# SensorPCBA_v0_1.net
KiCad netlist of a schematic drawn in Altium Designer
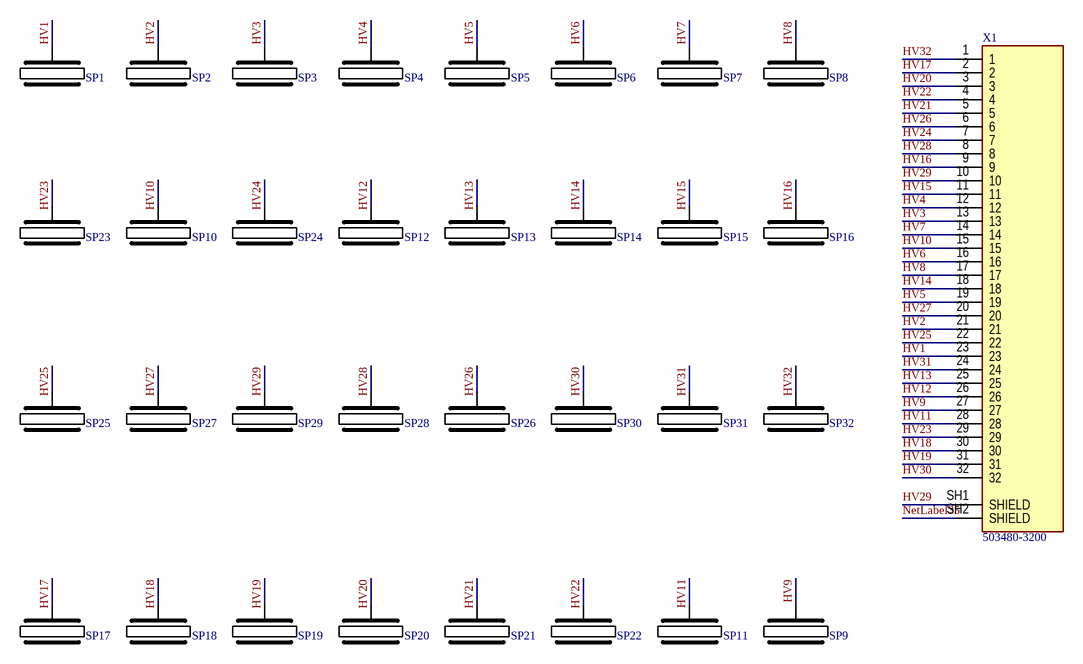
[diagram p0: SensorPCBA_v0.1.SchDoc]

(export (version "E")
  (design (tool "Eeschema 10.0.6"))
  (components
    (comp (ref "SP1")
      (value "SensorPAD")
      (footprint "Pump_via")
      (libsource (lib "SensorPCBA") (part "SensorPAD"))
    )
    (comp (ref "SP2")
      (value "SensorPAD")
      (footprint "Pump_via")
      (libsource (lib "SensorPCBA") (part "SensorPAD"))
    )
    (comp (ref "SP3")
      (value "SensorPAD")
      (footprint "Pump_via")
      (libsource (lib "SensorPCBA") (part "SensorPAD"))
    )
    (comp (ref "SP4")
      (value "SensorPAD")
      (footprint "Pump_via")
      (libsource (lib "SensorPCBA") (part "SensorPAD"))
    )
    (comp (ref "SP5")
      (value "SensorPAD")
      (footprint "Pump_via")
      (libsource (lib "SensorPCBA") (part "SensorPAD"))
    )
    (comp (ref "SP6")
      (value "SensorPAD")
      (footprint "Pump_via")
      (libsource (lib "SensorPCBA") (part "SensorPAD"))
    )
    (comp (ref "SP7")
      (value "SensorPAD")
      (footprint "Pump_via")
      (libsource (lib "SensorPCBA") (part "SensorPAD"))
    )
    (comp (ref "SP8")
      (value "SensorPAD")
      (footprint "Pump_via")
      (libsource (lib "SensorPCBA") (part "SensorPAD"))
    )
    (comp (ref "SP9")
      (value "SensorPAD")
      (footprint "Pump_via")
      (libsource (lib "SensorPCBA") (part "SensorPAD"))
    )
    (comp (ref "SP10")
      (value "SensorPAD")
      (footprint "Pump_via")
      (libsource (lib "SensorPCBA") (part "SensorPAD"))
    )
    (comp (ref "SP11")
      (value "SensorPAD")
      (footprint "Pump_via")
      (libsource (lib "SensorPCBA") (part "SensorPAD"))
    )
    (comp (ref "SP12")
      (value "SensorPAD")
      (footprint "Pump_via")
      (libsource (lib "SensorPCBA") (part "SensorPAD"))
    )
    (comp (ref "SP13")
      (value "SensorPAD")
      (footprint "Pump_via")
      (libsource (lib "SensorPCBA") (part "SensorPAD"))
    )
    (comp (ref "SP14")
      (value "SensorPAD")
      (footprint "Pump_via")
      (libsource (lib "SensorPCBA") (part "SensorPAD"))
    )
    (comp (ref "SP15")
      (value "SensorPAD")
      (footprint "Pump_via")
      (libsource (lib "SensorPCBA") (part "SensorPAD"))
    )
    (comp (ref "SP16")
      (value "SensorPAD")
      (footprint "Pump_via")
      (libsource (lib "SensorPCBA") (part "SensorPAD"))
    )
    (comp (ref "SP17")
      (value "SensorPAD")
      (footprint "Pump_via")
      (libsource (lib "SensorPCBA") (part "SensorPAD"))
    )
    (comp (ref "SP18")
      (value "SensorPAD")
      (footprint "Pump_via")
      (libsource (lib "SensorPCBA") (part "SensorPAD"))
    )
    (comp (ref "SP19")
      (value "SensorPAD")
      (footprint "Pump_via")
      (libsource (lib "SensorPCBA") (part "SensorPAD"))
    )
    (comp (ref "SP20")
      (value "SensorPAD")
      (footprint "Pump_via")
      (libsource (lib "SensorPCBA") (part "SensorPAD"))
    )
    (comp (ref "SP21")
      (value "SensorPAD")
      (footprint "Pump_via")
      (libsource (lib "SensorPCBA") (part "SensorPAD"))
    )
    (comp (ref "SP22")
      (value "SensorPAD")
      (footprint "Pump_via")
      (libsource (lib "SensorPCBA") (part "SensorPAD"))
    )
    (comp (ref "SP23")
      (value "SensorPAD")
      (footprint "Pump_via")
      (libsource (lib "SensorPCBA") (part "SensorPAD"))
    )
    (comp (ref "SP24")
      (value "SensorPAD")
      (footprint "Pump_via")
      (libsource (lib "SensorPCBA") (part "SensorPAD"))
    )
    (comp (ref "SP25")
      (value "SensorPAD")
      (footprint "Pump_via")
      (libsource (lib "SensorPCBA") (part "SensorPAD"))
    )
    (comp (ref "SP26")
      (value "SensorPAD")
      (footprint "Pump_via")
      (libsource (lib "SensorPCBA") (part "SensorPAD"))
    )
    (comp (ref "SP27")
      (value "SensorPAD")
      (footprint "Pump_via")
      (libsource (lib "SensorPCBA") (part "SensorPAD"))
    )
    (comp (ref "SP28")
      (value "SensorPAD")
      (footprint "Pump_via")
      (libsource (lib "SensorPCBA") (part "SensorPAD"))
    )
    (comp (ref "SP29")
      (value "SensorPAD")
      (footprint "Pump_via")
      (libsource (lib "SensorPCBA") (part "SensorPAD"))
    )
    (comp (ref "SP30")
      (value "SensorPAD")
      (footprint "Pump_via")
      (libsource (lib "SensorPCBA") (part "SensorPAD"))
    )
    (comp (ref "SP31")
      (value "SensorPAD")
      (footprint "Pump_via")
      (libsource (lib "SensorPCBA") (part "SensorPAD"))
    )
    (comp (ref "SP32")
      (value "SensorPAD")
      (footprint "Pump_via")
      (libsource (lib "SensorPCBA") (part "SensorPAD"))
    )
    (comp (ref "X1")
      (value "503480-3200")
      (footprint "MOLEX_503480-3200")
      (description "32 Position FFC, FPC Connector Contacts, Top and Bottom 0.020 (0.50mm) Surface Mount, Right Angle")
      (fields (field (name "MF") "Molex") (field (name "MP") "5034803200"))
      (libsource (lib "SensorPCBA") (part "503480-3200"))
    )
  )
  (nets
    (net (code "1") (name "/HV1") (class "Default")
      (node (ref "SP1") (pin "1") (pinfunction "Atop_1") (pintype "passive"))
      (node (ref "X1") (pin "23") (pinfunction "23_23") (pintype "passive"))
    )
    (net (code "2") (name "/HV2") (class "Default")
      (node (ref "SP2") (pin "1") (pinfunction "Atop_1") (pintype "passive"))
      (node (ref "X1") (pin "21") (pinfunction "21_21") (pintype "passive"))
    )
    (net (code "3") (name "/HV3") (class "Default")
      (node (ref "SP3") (pin "1") (pinfunction "Atop_1") (pintype "passive"))
      (node (ref "X1") (pin "13") (pinfunction "13_13") (pintype "passive"))
    )
    (net (code "4") (name "/HV4") (class "Default")
      (node (ref "SP4") (pin "1") (pinfunction "Atop_1") (pintype "passive"))
      (node (ref "X1") (pin "12") (pinfunction "12_12") (pintype "passive"))
    )
    (net (code "5") (name "/HV5") (class "Default")
      (node (ref "SP5") (pin "1") (pinfunction "Atop_1") (pintype "passive"))
      (node (ref "X1") (pin "19") (pinfunction "19_19") (pintype "passive"))
    )
    (net (code "6") (name "/HV6") (class "Default")
      (node (ref "SP6") (pin "1") (pinfunction "Atop_1") (pintype "passive"))
      (node (ref "X1") (pin "16") (pinfunction "16_16") (pintype "passive"))
    )
    (net (code "7") (name "/HV7") (class "Default")
      (node (ref "SP7") (pin "1") (pinfunction "Atop_1") (pintype "passive"))
      (node (ref "X1") (pin "14") (pinfunction "14_14") (pintype "passive"))
    )
    (net (code "8") (name "/HV8") (class "Default")
      (node (ref "SP8") (pin "1") (pinfunction "Atop_1") (pintype "passive"))
      (node (ref "X1") (pin "17") (pinfunction "17_17") (pintype "passive"))
    )
    (net (code "9") (name "/HV9") (class "Default")
      (node (ref "SP9") (pin "1") (pinfunction "Atop_1") (pintype "passive"))
      (node (ref "X1") (pin "27") (pinfunction "27_27") (pintype "passive"))
    )
    (net (code "10") (name "/HV10") (class "Default")
      (node (ref "SP10") (pin "1") (pinfunction "Atop_1") (pintype "passive"))
      (node (ref "X1") (pin "15") (pinfunction "15_15") (pintype "passive"))
    )
    (net (code "11") (name "/HV11") (class "Default")
      (node (ref "SP11") (pin "1") (pinfunction "Atop_1") (pintype "passive"))
      (node (ref "X1") (pin "28") (pinfunction "28_28") (pintype "passive"))
    )
    (net (code "12") (name "/HV12") (class "Default")
      (node (ref "SP12") (pin "1") (pinfunction "Atop_1") (pintype "passive"))
      (node (ref "X1") (pin "26") (pinfunction "26_26") (pintype "passive"))
    )
    (net (code "13") (name "/HV13") (class "Default")
      (node (ref "SP13") (pin "1") (pinfunction "Atop_1") (pintype "passive"))
      (node (ref "X1") (pin "25") (pinfunction "25_25") (pintype "passive"))
    )
    (net (code "14") (name "/HV14") (class "Default")
      (node (ref "SP14") (pin "1") (pinfunction "Atop_1") (pintype "passive"))
      (node (ref "X1") (pin "18") (pinfunction "18_18") (pintype "passive"))
    )
    (net (code "15") (name "/HV15") (class "Default")
      (node (ref "SP15") (pin "1") (pinfunction "Atop_1") (pintype "passive"))
      (node (ref "X1") (pin "11") (pinfunction "11_11") (pintype "passive"))
    )
    (net (code "16") (name "/HV16") (class "Default")
      (node (ref "SP16") (pin "1") (pinfunction "Atop_1") (pintype "passive"))
      (node (ref "X1") (pin "9") (pinfunction "9_9") (pintype "passive"))
    )
    (net (code "17") (name "/HV17") (class "Default")
      (node (ref "SP17") (pin "1") (pinfunction "Atop_1") (pintype "passive"))
      (node (ref "X1") (pin "2") (pinfunction "2_2") (pintype "passive"))
    )
    (net (code "18") (name "/HV18") (class "Default")
      (node (ref "SP18") (pin "1") (pinfunction "Atop_1") (pintype "passive"))
      (node (ref "X1") (pin "30") (pinfunction "30_30") (pintype "passive"))
    )
    (net (code "19") (name "/HV19") (class "Default")
      (node (ref "SP19") (pin "1") (pinfunction "Atop_1") (pintype "passive"))
      (node (ref "X1") (pin "31") (pinfunction "31_31") (pintype "passive"))
    )
    (net (code "20") (name "/HV20") (class "Default")
      (node (ref "SP20") (pin "1") (pinfunction "Atop_1") (pintype "passive"))
      (node (ref "X1") (pin "3") (pinfunction "3_3") (pintype "passive"))
    )
    (net (code "21") (name "/HV21") (class "Default")
      (node (ref "SP21") (pin "1") (pinfunction "Atop_1") (pintype "passive"))
      (node (ref "X1") (pin "5") (pinfunction "5_5") (pintype "passive"))
    )
    (net (code "22") (name "/HV22") (class "Default")
      (node (ref "SP22") (pin "1") (pinfunction "Atop_1") (pintype "passive"))
      (node (ref "X1") (pin "4") (pinfunction "4_4") (pintype "passive"))
    )
    (net (code "23") (name "/HV23") (class "Default")
      (node (ref "SP23") (pin "1") (pinfunction "Atop_1") (pintype "passive"))
      (node (ref "X1") (pin "29") (pinfunction "29_29") (pintype "passive"))
    )
    (net (code "24") (name "/HV24") (class "Default")
      (node (ref "SP24") (pin "1") (pinfunction "Atop_1") (pintype "passive"))
      (node (ref "X1") (pin "7") (pinfunction "7_7") (pintype "passive"))
    )
    (net (code "25") (name "/HV25") (class "Default")
      (node (ref "SP25") (pin "1") (pinfunction "Atop_1") (pintype "passive"))
      (node (ref "X1") (pin "22") (pinfunction "22_22") (pintype "passive"))
    )
    (net (code "26") (name "/HV26") (class "Default")
      (node (ref "SP26") (pin "1") (pinfunction "Atop_1") (pintype "passive"))
      (node (ref "X1") (pin "6") (pinfunction "6_6") (pintype "passive"))
    )
    (net (code "27") (name "/HV27") (class "Default")
      (node (ref "SP27") (pin "1") (pinfunction "Atop_1") (pintype "passive"))
      (node (ref "X1") (pin "20") (pinfunction "20_20") (pintype "passive"))
    )
    (net (code "28") (name "/HV28") (class "Default")
      (node (ref "SP28") (pin "1") (pinfunction "Atop_1") (pintype "passive"))
      (node (ref "X1") (pin "8") (pinfunction "8_8") (pintype "passive"))
    )
    (net (code "29") (name "/HV29") (class "Default")
      (node (ref "SP29") (pin "1") (pinfunction "Atop_1") (pintype "passive"))
      (node (ref "X1") (pin "10") (pinfunction "10_10") (pintype "passive"))
      (node (ref "X1") (pin "SH1") (pinfunction "SHIELD_SH1") (pintype "passive"))
    )
    (net (code "30") (name "/HV30") (class "Default")
      (node (ref "SP30") (pin "1") (pinfunction "Atop_1") (pintype "passive"))
      (node (ref "X1") (pin "32") (pinfunction "32_32") (pintype "passive"))
    )
    (net (code "31") (name "/HV31") (class "Default")
      (node (ref "SP31") (pin "1") (pinfunction "Atop_1") (pintype "passive"))
      (node (ref "X1") (pin "24") (pinfunction "24_24") (pintype "passive"))
    )
    (net (code "32") (name "/HV32") (class "Default")
      (node (ref "SP32") (pin "1") (pinfunction "Atop_1") (pintype "passive"))
      (node (ref "X1") (pin "1") (pinfunction "1_1") (pintype "passive"))
    )
    (net (code "33") (name "/NetLabel35") (class "Default")
      (node (ref "X1") (pin "SH2") (pinfunction "SHIELD_SH2") (pintype "passive"))
    )
  )
)
